# writer_attiny10.net
KiCad netlist of a schematic drawn in EAGLE
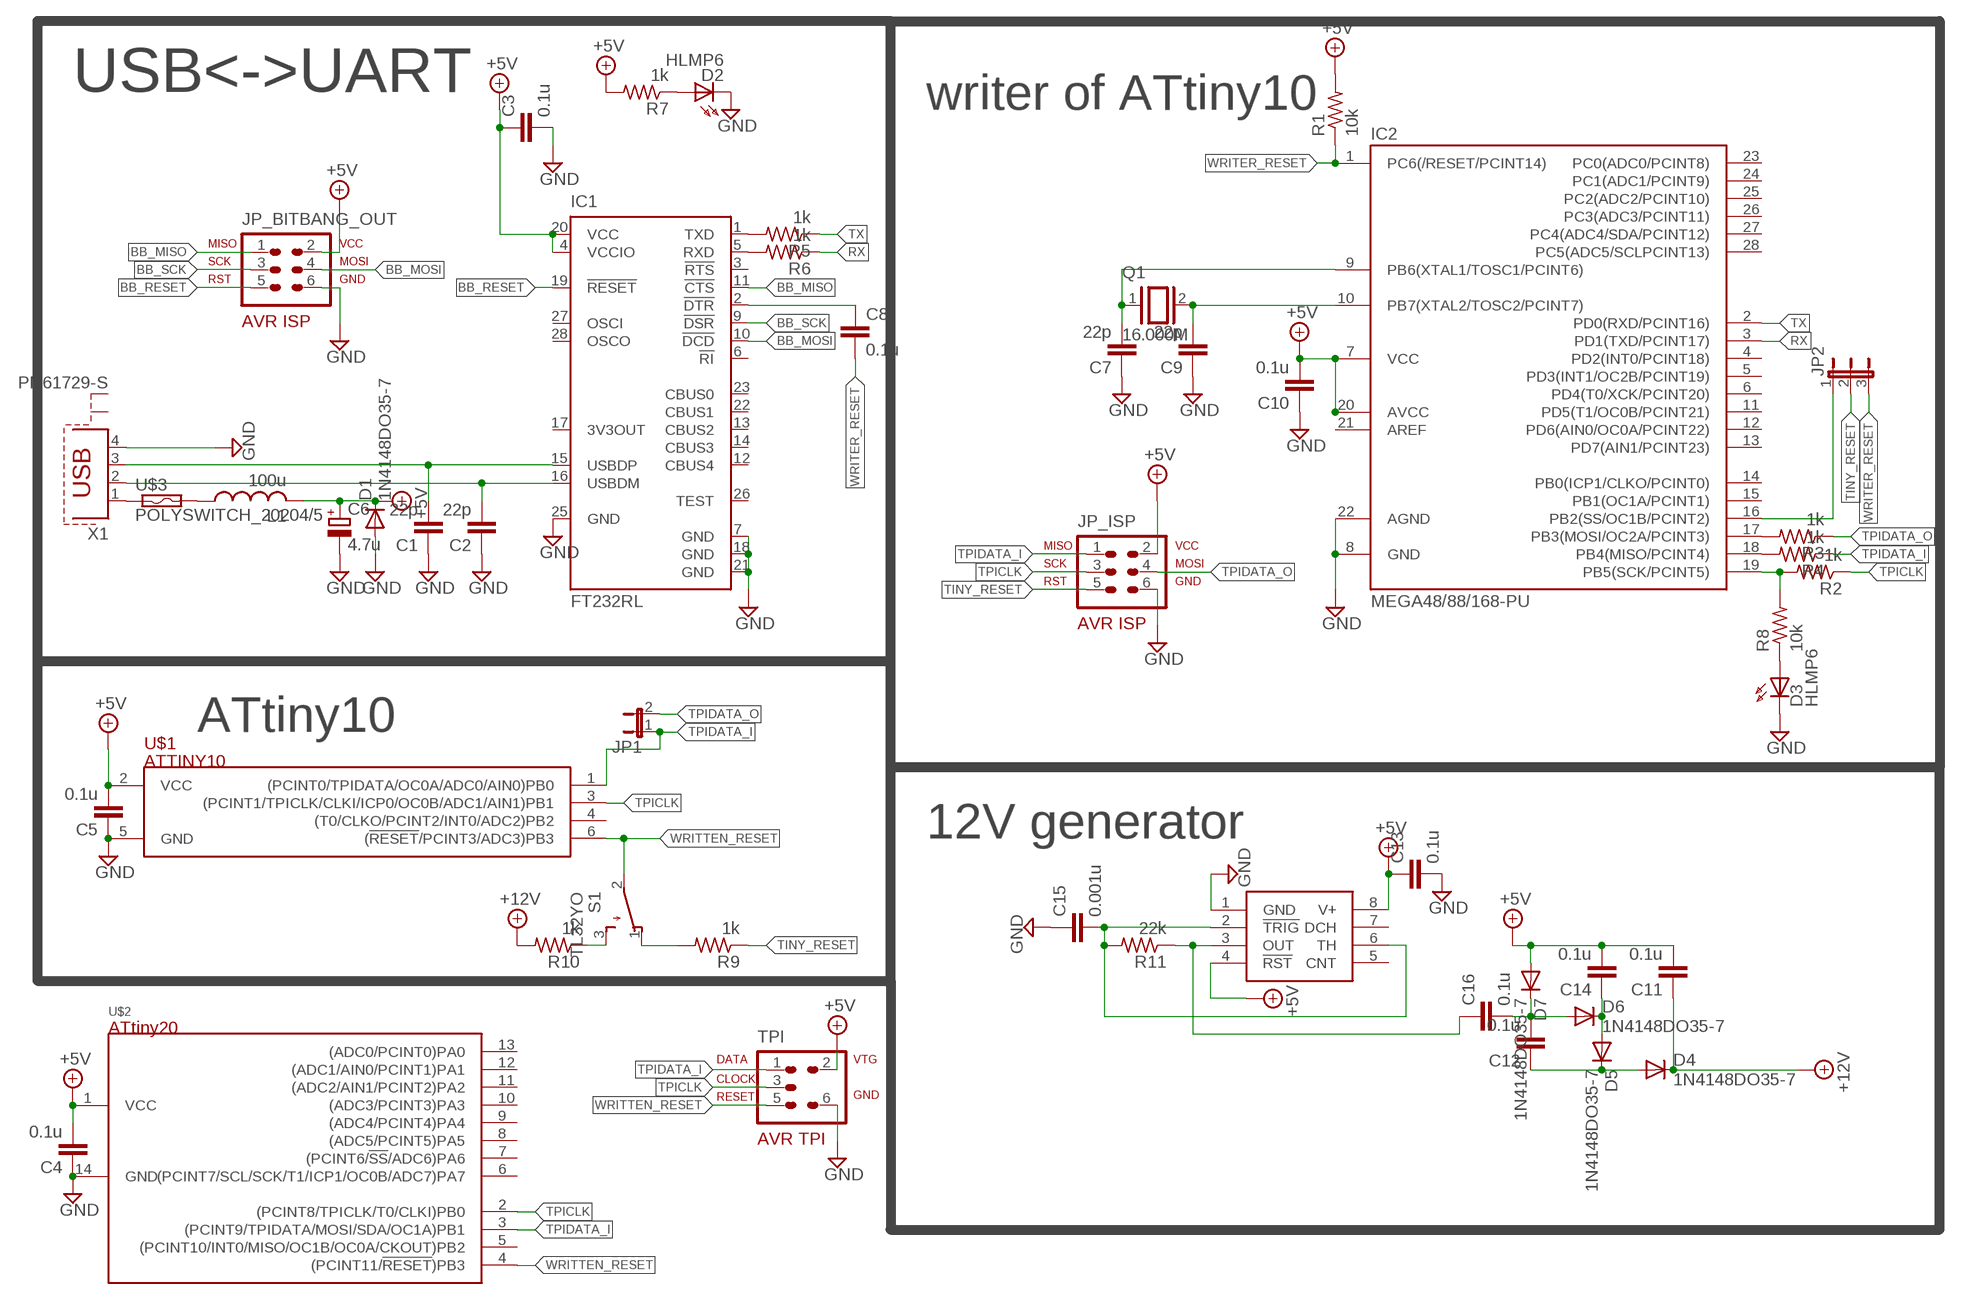
[diagram p0: schematic, sheet 1]

(export (version "E")
  (design (tool "Eeschema 10.0.6"))
  (components
    (comp (ref "C1")
      (value "22p")
      (footprint "eagle-import:C0603")
      (libsource (lib "eagle-import") (part "C-EUC0603"))
    )
    (comp (ref "C2")
      (value "22p")
      (footprint "eagle-import:C0603")
      (libsource (lib "eagle-import") (part "C-EUC0603"))
    )
    (comp (ref "C3")
      (value "0.1u")
      (footprint "eagle-import:C0603")
      (libsource (lib "eagle-import") (part "C-EUC0603"))
    )
    (comp (ref "C4")
      (value "0.1u")
      (footprint "eagle-import:C0603")
      (libsource (lib "eagle-import") (part "C-EUC0603"))
    )
    (comp (ref "C5")
      (value "0.1u")
      (footprint "eagle-import:C0603")
      (libsource (lib "eagle-import") (part "C-EUC0603"))
    )
    (comp (ref "C6")
      (value "4.7u")
      (footprint "eagle-import:CT3216")
      (libsource (lib "eagle-import") (part "CPOL-EUCT3216"))
    )
    (comp (ref "C7")
      (value "22p")
      (footprint "eagle-import:C0603")
      (libsource (lib "eagle-import") (part "C-EUC0603"))
    )
    (comp (ref "C8")
      (value "0.1u")
      (footprint "eagle-import:C0603")
      (libsource (lib "eagle-import") (part "C-EUC0603"))
    )
    (comp (ref "C9")
      (value "22p")
      (footprint "eagle-import:C0603")
      (libsource (lib "eagle-import") (part "C-EUC0603"))
    )
    (comp (ref "C10")
      (value "0.1u")
      (footprint "eagle-import:C0603")
      (libsource (lib "eagle-import") (part "C-EUC0603"))
    )
    (comp (ref "C11")
      (value "0.1u")
      (footprint "eagle-import:C0603")
      (libsource (lib "eagle-import") (part "C-EUC0603"))
    )
    (comp (ref "C12")
      (value "0.1u")
      (footprint "eagle-import:C0603")
      (libsource (lib "eagle-import") (part "C-EUC0603"))
    )
    (comp (ref "C13")
      (value "0.1u")
      (footprint "eagle-import:C0603")
      (libsource (lib "eagle-import") (part "C-EUC0603"))
    )
    (comp (ref "C14")
      (value "0.1u")
      (footprint "eagle-import:C0603")
      (libsource (lib "eagle-import") (part "C-EUC0603"))
    )
    (comp (ref "C15")
      (value "0.001u")
      (footprint "eagle-import:C0603")
      (libsource (lib "eagle-import") (part "C-EUC0603"))
    )
    (comp (ref "C16")
      (value "0.1u")
      (footprint "eagle-import:C0603")
      (libsource (lib "eagle-import") (part "C-EUC0603"))
    )
    (comp (ref "D1")
      (value "1N4148DO35-7")
      (footprint "eagle-import:DO35-7")
      (libsource (lib "eagle-import") (part "1N4148DO35-7"))
    )
    (comp (ref "D2")
      (value "HLMP6")
      (footprint "eagle-import:HLMP6")
      (fields
        (field (name "MF") "AGILENT TECHNOLOGIES")
        (field (name "MPN") "HLMP-6500")
        (field (name "MF_1") "AGILENT TECHNOLOGIES")
        (field (name "MPN_1") "HLMP-6500")
        (field (name "OC_FARNELL") "1652490")
        (field (name "OC_NEWARK") "40K0088")
      )
      (libsource (lib "eagle-import") (part "HLMP6"))
    )
    (comp (ref "D3")
      (value "HLMP6")
      (footprint "eagle-import:HLMP6")
      (fields (field (name "MF") "AGILENT TECHNOLOGIES") (field (name "MPN") "HLMP-6500"))
      (libsource (lib "eagle-import") (part "HLMP6"))
    )
    (comp (ref "D4")
      (value "1N4148DO35-7")
      (footprint "eagle-import:DO35-7")
      (libsource (lib "eagle-import") (part "1N4148DO35-7"))
    )
    (comp (ref "D5")
      (value "1N4148DO35-7")
      (footprint "eagle-import:DO35-7")
      (libsource (lib "eagle-import") (part "1N4148DO35-7"))
    )
    (comp (ref "D6")
      (value "1N4148DO35-7")
      (footprint "eagle-import:DO35-7")
      (libsource (lib "eagle-import") (part "1N4148DO35-7"))
    )
    (comp (ref "D7")
      (value "1N4148DO35-7")
      (footprint "eagle-import:DO35-7")
      (libsource (lib "eagle-import") (part "1N4148DO35-7"))
    )
    (comp (ref "IC1")
      (value "FT232RL")
      (footprint "eagle-import:SSOP28")
      (libsource (lib "eagle-import") (part "FT232RL"))
    )
    (comp (ref "IC2")
      (value "MEGA48/88/168-PU")
      (footprint "eagle-import:DIL28-3")
      (libsource (lib "eagle-import") (part "MEGA48/88/168-PU"))
    )
    (comp (ref "IC3")
      (value "LMC555")
      (footprint "eagle-import:DIL08")
      (libsource (lib "eagle-import") (part "LMC555"))
    )
    (comp (ref "JP1")
      (value "JP1E")
      (footprint "eagle-import:JP1")
      (libsource (lib "eagle-import") (part "JP1E"))
    )
    (comp (ref "JP2")
      (value "JP2E")
      (footprint "eagle-import:JP2")
      (libsource (lib "eagle-import") (part "JP2E"))
    )
    (comp (ref "JP_BITBANG_OUT")
      (value "AVR-ISP-6VERT")
      (footprint "eagle-import:AVR-ISP-6")
      (libsource (lib "eagle-import") (part "AVR-ISP-6VERT"))
    )
    (comp (ref "JP_ISP")
      (value "AVR-ISP-6VERT")
      (footprint "eagle-import:AVR-ISP-6")
      (libsource (lib "eagle-import") (part "AVR-ISP-6VERT"))
    )
    (comp (ref "L1")
      (value "100u")
      (footprint "eagle-import:0207_10")
      (libsource (lib "eagle-import") (part "L-US0207/10"))
    )
    (comp (ref "Q1")
      (value "16.000M")
      (footprint "eagle-import:QS")
      (libsource (lib "eagle-import") (part "XTAL/S"))
    )
    (comp (ref "R1")
      (value "10k")
      (footprint "eagle-import:R0603")
      (libsource (lib "eagle-import") (part "R-US_R0603"))
    )
    (comp (ref "R2")
      (value "1k")
      (footprint "eagle-import:R0603")
      (libsource (lib "eagle-import") (part "R-US_R0603"))
    )
    (comp (ref "R3")
      (value "1k")
      (footprint "eagle-import:R0603")
      (libsource (lib "eagle-import") (part "R-US_R0603"))
    )
    (comp (ref "R4")
      (value "1k")
      (footprint "eagle-import:R0603")
      (libsource (lib "eagle-import") (part "R-US_R0603"))
    )
    (comp (ref "R5")
      (value "1k")
      (footprint "eagle-import:R0603")
      (libsource (lib "eagle-import") (part "R-US_R0603"))
    )
    (comp (ref "R6")
      (value "1k")
      (footprint "eagle-import:R0603")
      (libsource (lib "eagle-import") (part "R-US_R0603"))
    )
    (comp (ref "R7")
      (value "1k")
      (footprint "eagle-import:R0603")
      (libsource (lib "eagle-import") (part "R-US_R0603"))
    )
    (comp (ref "R8")
      (value "10k")
      (footprint "eagle-import:R0603")
      (libsource (lib "eagle-import") (part "R-US_R0603"))
    )
    (comp (ref "R9")
      (value "1k")
      (footprint "eagle-import:R0603")
      (libsource (lib "eagle-import") (part "R-US_R0603"))
    )
    (comp (ref "R10")
      (value "1k")
      (footprint "eagle-import:R0603")
      (libsource (lib "eagle-import") (part "R-US_R0603"))
    )
    (comp (ref "R11")
      (value "22k")
      (footprint "eagle-import:R0603")
      (libsource (lib "eagle-import") (part "R-US_R0603"))
    )
    (comp (ref "S1")
      (value "TL32YO")
      (footprint "eagle-import:TL3XYO")
      (libsource (lib "eagle-import") (part "TL32YO"))
    )
    (comp (ref "TPI")
      (value "AVR-TPIVERT")
      (footprint "eagle-import:AVR-ISP-6")
      (libsource (lib "eagle-import") (part "AVR-TPIVERT"))
    )
    (comp (ref "U$1")
      (value "ATTINY10")
      (footprint "eagle-import:SOT-23")
      (libsource (lib "eagle-import") (part "ATTINY10"))
    )
    (comp (ref "U$2")
      (value "ATTINY20")
      (footprint "eagle-import:SOIC14")
      (libsource (lib "eagle-import") (part "ATTINY20"))
    )
    (comp (ref "U$3")
      (value "POLYSWITCH_20204/5")
      (footprint "eagle-import:0204_5")
      (libsource (lib "eagle-import") (part "POLYSWITCH_20204/5"))
    )
    (comp (ref "X1")
      (value "PN61729-S")
      (footprint "eagle-import:PN61729-S")
      (libsource (lib "eagle-import") (part "PN61729-S"))
    )
  )
  (nets
    (net (code "1") (name "+5V") (class "Default")
      (node (ref "C10") (pin "2") (pinfunction "2_2") (pintype "passive"))
      (node (ref "C11") (pin "2") (pinfunction "2_2") (pintype "passive"))
      (node (ref "C13") (pin "1") (pinfunction "1_1") (pintype "passive"))
      (node (ref "C14") (pin "2") (pinfunction "2_2") (pintype "passive"))
      (node (ref "C3") (pin "1") (pinfunction "1_1") (pintype "passive"))
      (node (ref "C4") (pin "2") (pinfunction "2_2") (pintype "passive"))
      (node (ref "C5") (pin "2") (pinfunction "2_2") (pintype "passive"))
      (node (ref "C6") (pin "+") (pinfunction "+_+") (pintype "passive"))
      (node (ref "D1") (pin "C") (pinfunction "C_C") (pintype "passive"))
      (node (ref "D7") (pin "A") (pinfunction "A_A") (pintype "passive"))
      (node (ref "IC1") (pin "20") (pinfunction "VCC_20") (pintype "power_in"))
      (node (ref "IC1") (pin "4") (pinfunction "VCCIO_4") (pintype "power_in"))
      (node (ref "IC2") (pin "20") (pinfunction "AVCC_20") (pintype "passive"))
      (node (ref "IC2") (pin "7") (pinfunction "VCC_7") (pintype "power_in"))
      (node (ref "IC3") (pin "4") (pinfunction "~{RST}_4") (pintype "bidirectional"))
      (node (ref "IC3") (pin "8") (pinfunction "V+_8") (pintype "bidirectional"))
      (node (ref "JP_BITBANG_OUT") (pin "2") (pinfunction "2_2") (pintype "passive"))
      (node (ref "JP_ISP") (pin "2") (pinfunction "2_2") (pintype "passive"))
      (node (ref "L1") (pin "2") (pinfunction "2_2") (pintype "passive"))
      (node (ref "R1") (pin "2") (pinfunction "2_2") (pintype "passive"))
      (node (ref "R7") (pin "2") (pinfunction "2_2") (pintype "passive"))
      (node (ref "TPI") (pin "2") (pinfunction "2_2") (pintype "passive"))
      (node (ref "U$1") (pin "2") (pinfunction "VCC_2") (pintype "power_in"))
      (node (ref "U$2") (pin "1") (pinfunction "VCC_1") (pintype "bidirectional"))
    )
    (net (code "2") (name "+12V") (class "Default")
      (node (ref "C11") (pin "1") (pinfunction "1_1") (pintype "passive"))
      (node (ref "D4") (pin "C") (pinfunction "C_C") (pintype "passive"))
      (node (ref "R10") (pin "2") (pinfunction "2_2") (pintype "passive"))
    )
    (net (code "3") (name "BB_MISO") (class "Default")
      (node (ref "IC1") (pin "11") (pinfunction "~{CTS}_11") (pintype "input"))
      (node (ref "JP_BITBANG_OUT") (pin "1") (pinfunction "1_1") (pintype "passive"))
    )
    (net (code "4") (name "BB_MOSI") (class "Default")
      (node (ref "IC1") (pin "10") (pinfunction "~{DCD}_10") (pintype "input"))
      (node (ref "JP_BITBANG_OUT") (pin "4") (pinfunction "4_4") (pintype "passive"))
    )
    (net (code "5") (name "BB_RESET") (class "Default")
      (node (ref "IC1") (pin "19") (pinfunction "~{RESET}_19") (pintype "input"))
      (node (ref "JP_BITBANG_OUT") (pin "5") (pinfunction "5_5") (pintype "passive"))
    )
    (net (code "6") (name "BB_SCK") (class "Default")
      (node (ref "IC1") (pin "9") (pinfunction "~{DSR}_9") (pintype "input"))
      (node (ref "JP_BITBANG_OUT") (pin "3") (pinfunction "3_3") (pintype "passive"))
    )
    (net (code "7") (name "GND") (class "Default")
      (node (ref "C1") (pin "1") (pinfunction "1_1") (pintype "passive"))
      (node (ref "C10") (pin "1") (pinfunction "1_1") (pintype "passive"))
      (node (ref "C13") (pin "2") (pinfunction "2_2") (pintype "passive"))
      (node (ref "C15") (pin "1") (pinfunction "1_1") (pintype "passive"))
      (node (ref "C2") (pin "1") (pinfunction "1_1") (pintype "passive"))
      (node (ref "C3") (pin "2") (pinfunction "2_2") (pintype "passive"))
      (node (ref "C4") (pin "1") (pinfunction "1_1") (pintype "passive"))
      (node (ref "C5") (pin "1") (pinfunction "1_1") (pintype "passive"))
      (node (ref "C6") (pin "-") (pinfunction "-_-") (pintype "passive"))
      (node (ref "C7") (pin "1") (pinfunction "1_1") (pintype "passive"))
      (node (ref "C9") (pin "1") (pinfunction "1_1") (pintype "passive"))
      (node (ref "D1") (pin "A") (pinfunction "A_A") (pintype "passive"))
      (node (ref "D2") (pin "K") (pinfunction "K_K") (pintype "passive"))
      (node (ref "D3") (pin "K") (pinfunction "K_K") (pintype "passive"))
      (node (ref "IC1") (pin "18") (pinfunction "GND_18") (pintype "power_in"))
      (node (ref "IC1") (pin "21") (pinfunction "GND_21") (pintype "power_in"))
      (node (ref "IC1") (pin "25") (pinfunction "GND_25") (pintype "power_in"))
      (node (ref "IC1") (pin "7") (pinfunction "GND_7") (pintype "power_in"))
      (node (ref "IC2") (pin "22") (pinfunction "AGND_22") (pintype "power_in"))
      (node (ref "IC2") (pin "8") (pinfunction "GND_8") (pintype "power_in"))
      (node (ref "IC3") (pin "1") (pinfunction "GND_1") (pintype "bidirectional"))
      (node (ref "JP_BITBANG_OUT") (pin "6") (pinfunction "6_6") (pintype "passive"))
      (node (ref "JP_ISP") (pin "6") (pinfunction "6_6") (pintype "passive"))
      (node (ref "TPI") (pin "6") (pinfunction "6_6") (pintype "passive"))
      (node (ref "U$1") (pin "5") (pinfunction "GND_5") (pintype "power_in"))
      (node (ref "U$2") (pin "14") (pinfunction "GND_14") (pintype "bidirectional"))
      (node (ref "X1") (pin "4") (pinfunction "4_4") (pintype "passive"))
    )
    (net (code "8") (name "Net-(C12-Pad1)") (class "Default")
      (node (ref "C12") (pin "1") (pinfunction "1_1") (pintype "passive"))
      (node (ref "D4") (pin "A") (pinfunction "A_A") (pintype "passive"))
      (node (ref "D5") (pin "C") (pinfunction "C_C") (pintype "passive"))
    )
    (net (code "9") (name "Net-(C12-Pad2)") (class "Default")
      (node (ref "C12") (pin "2") (pinfunction "2_2") (pintype "passive"))
      (node (ref "C16") (pin "2") (pinfunction "2_2") (pintype "passive"))
      (node (ref "D6") (pin "A") (pinfunction "A_A") (pintype "passive"))
      (node (ref "D7") (pin "C") (pinfunction "C_C") (pintype "passive"))
    )
    (net (code "10") (name "Net-(C14-Pad1)") (class "Default")
      (node (ref "C14") (pin "1") (pinfunction "1_1") (pintype "passive"))
      (node (ref "D5") (pin "A") (pinfunction "A_A") (pintype "passive"))
      (node (ref "D6") (pin "C") (pinfunction "C_C") (pintype "passive"))
    )
    (net (code "11") (name "Net-(D2-PadA)") (class "Default")
      (node (ref "D2") (pin "A") (pinfunction "A_A") (pintype "passive"))
      (node (ref "R7") (pin "1") (pinfunction "1_1") (pintype "passive"))
    )
    (net (code "12") (name "Net-(D3-PadA)") (class "Default")
      (node (ref "D3") (pin "A") (pinfunction "A_A") (pintype "passive"))
      (node (ref "R8") (pin "1") (pinfunction "1_1") (pintype "passive"))
    )
    (net (code "13") (name "Net-(IC1-RXD)") (class "Default")
      (node (ref "IC1") (pin "5") (pinfunction "RXD_5") (pintype "input"))
      (node (ref "R6") (pin "2") (pinfunction "2_2") (pintype "passive"))
    )
    (net (code "14") (name "Net-(IC1-TXD)") (class "Default")
      (node (ref "IC1") (pin "1") (pinfunction "TXD_1") (pintype "output"))
      (node (ref "R5") (pin "2") (pinfunction "2_2") (pintype "passive"))
    )
    (net (code "15") (name "Net-(IC1-USBDM)") (class "Default")
      (node (ref "C2") (pin "2") (pinfunction "2_2") (pintype "passive"))
      (node (ref "IC1") (pin "16") (pinfunction "USBDM_16") (pintype "bidirectional"))
      (node (ref "X1") (pin "2") (pinfunction "2_2") (pintype "passive"))
    )
    (net (code "16") (name "Net-(IC1-USBDP)") (class "Default")
      (node (ref "C1") (pin "2") (pinfunction "2_2") (pintype "passive"))
      (node (ref "IC1") (pin "15") (pinfunction "USBDP_15") (pintype "bidirectional"))
      (node (ref "X1") (pin "3") (pinfunction "3_3") (pintype "passive"))
    )
    (net (code "17") (name "Net-(IC1-~{DTR})") (class "Default")
      (node (ref "C8") (pin "1") (pinfunction "1_1") (pintype "passive"))
      (node (ref "IC1") (pin "2") (pinfunction "~{DTR}_2") (pintype "output"))
    )
    (net (code "18") (name "Net-(IC2-PB2(SS{slash}OC1B{slash}PCINT2))") (class "Default")
      (node (ref "IC2") (pin "16") (pinfunction "PB2(SS/OC1B/PCINT2)_16") (pintype "bidirectional"))
      (node (ref "JP2") (pin "1") (pinfunction "1_1") (pintype "passive"))
    )
    (net (code "19") (name "Net-(IC2-PB3(MOSI{slash}OC2A{slash}PCINT3))") (class "Default")
      (node (ref "IC2") (pin "17") (pinfunction "PB3(MOSI/OC2A/PCINT3)_17") (pintype "bidirectional"))
      (node (ref "R3") (pin "2") (pinfunction "2_2") (pintype "passive"))
    )
    (net (code "20") (name "Net-(IC2-PB4(MISO{slash}PCINT4))") (class "Default")
      (node (ref "IC2") (pin "18") (pinfunction "PB4(MISO/PCINT4)_18") (pintype "bidirectional"))
      (node (ref "R4") (pin "2") (pinfunction "2_2") (pintype "passive"))
    )
    (net (code "21") (name "Net-(IC2-PB5(SCK{slash}PCINT5))") (class "Default")
      (node (ref "IC2") (pin "19") (pinfunction "PB5(SCK/PCINT5)_19") (pintype "bidirectional"))
      (node (ref "R2") (pin "2") (pinfunction "2_2") (pintype "passive"))
      (node (ref "R8") (pin "2") (pinfunction "2_2") (pintype "passive"))
    )
    (net (code "22") (name "Net-(IC2-PB6(XTAL1{slash}TOSC1{slash}PCINT6))") (class "Default")
      (node (ref "C7") (pin "2") (pinfunction "2_2") (pintype "passive"))
      (node (ref "IC2") (pin "9") (pinfunction "PB6(XTAL1/TOSC1/PCINT6)_9") (pintype "bidirectional"))
      (node (ref "Q1") (pin "1") (pinfunction "1_1") (pintype "passive"))
    )
    (net (code "23") (name "Net-(IC2-PB7(XTAL2{slash}TOSC2{slash}PCINT7))") (class "Default")
      (node (ref "C9") (pin "2") (pinfunction "2_2") (pintype "passive"))
      (node (ref "IC2") (pin "10") (pinfunction "PB7(XTAL2/TOSC2/PCINT7)_10") (pintype "bidirectional"))
      (node (ref "Q1") (pin "2") (pinfunction "2_2") (pintype "passive"))
    )
    (net (code "24") (name "Net-(IC3-OUT)") (class "Default")
      (node (ref "C16") (pin "1") (pinfunction "1_1") (pintype "passive"))
      (node (ref "IC3") (pin "3") (pinfunction "OUT_3") (pintype "bidirectional"))
      (node (ref "R11") (pin "1") (pinfunction "1_1") (pintype "passive"))
    )
    (net (code "25") (name "Net-(IC3-TH)") (class "Default")
      (node (ref "C15") (pin "2") (pinfunction "2_2") (pintype "passive"))
      (node (ref "IC3") (pin "2") (pinfunction "~{TRIG}_2") (pintype "bidirectional"))
      (node (ref "IC3") (pin "6") (pinfunction "TH_6") (pintype "bidirectional"))
      (node (ref "R11") (pin "2") (pinfunction "2_2") (pintype "passive"))
    )
    (net (code "26") (name "Net-(L1-Pad1)") (class "Default")
      (node (ref "L1") (pin "1") (pinfunction "1_1") (pintype "passive"))
      (node (ref "U$3") (pin "2") (pinfunction "2_2") (pintype "passive"))
    )
    (net (code "27") (name "Net-(S1-O)") (class "Default")
      (node (ref "R9") (pin "2") (pinfunction "2_2") (pintype "passive"))
      (node (ref "S1") (pin "1") (pinfunction "O_1") (pintype "passive"))
    )
    (net (code "28") (name "Net-(S1-S)") (class "Default")
      (node (ref "R10") (pin "1") (pinfunction "1_1") (pintype "passive"))
      (node (ref "S1") (pin "3") (pinfunction "S_3") (pintype "passive"))
    )
    (net (code "29") (name "Net-(U$3-Pad1)") (class "Default")
      (node (ref "U$3") (pin "1") (pinfunction "1_1") (pintype "passive"))
      (node (ref "X1") (pin "1") (pinfunction "1_1") (pintype "passive"))
    )
    (net (code "30") (name "RX") (class "Default")
      (node (ref "IC2") (pin "3") (pinfunction "PD1(TXD/PCINT17)_3") (pintype "bidirectional"))
      (node (ref "R6") (pin "1") (pinfunction "1_1") (pintype "passive"))
    )
    (net (code "31") (name "TINY_RESET") (class "Default")
      (node (ref "JP2") (pin "2") (pinfunction "2_2") (pintype "passive"))
      (node (ref "JP_ISP") (pin "5") (pinfunction "5_5") (pintype "passive"))
      (node (ref "R9") (pin "1") (pinfunction "1_1") (pintype "passive"))
    )
    (net (code "32") (name "TPICLK") (class "Default")
      (node (ref "JP_ISP") (pin "3") (pinfunction "3_3") (pintype "passive"))
      (node (ref "R2") (pin "1") (pinfunction "1_1") (pintype "passive"))
      (node (ref "TPI") (pin "3") (pinfunction "3_3") (pintype "passive"))
      (node (ref "U$1") (pin "3") (pinfunction "(PCINT1/TPICLK/CLKI/ICP0/OC0B/ADC1/AIN1)PB1_3") (pintype "bidirectional"))
      (node (ref "U$2") (pin "2") (pinfunction "(PCINT8/TPICLK/T0/CLKI)PB0_2") (pintype "bidirectional"))
    )
    (net (code "33") (name "TPIDATA_I") (class "Default")
      (node (ref "JP1") (pin "1") (pinfunction "1_1") (pintype "passive"))
      (node (ref "JP_ISP") (pin "1") (pinfunction "1_1") (pintype "passive"))
      (node (ref "R4") (pin "1") (pinfunction "1_1") (pintype "passive"))
      (node (ref "TPI") (pin "1") (pinfunction "1_1") (pintype "passive"))
      (node (ref "U$1") (pin "1") (pinfunction "(PCINT0/TPIDATA/OC0A/ADC0/AIN0)PB0_1") (pintype "bidirectional"))
      (node (ref "U$2") (pin "3") (pinfunction "(PCINT9/TPIDATA/MOSI/SDA/OC1A)PB1_3") (pintype "bidirectional"))
    )
    (net (code "34") (name "TPIDATA_O") (class "Default")
      (node (ref "JP1") (pin "2") (pinfunction "2_2") (pintype "passive"))
      (node (ref "JP_ISP") (pin "4") (pinfunction "4_4") (pintype "passive"))
      (node (ref "R3") (pin "1") (pinfunction "1_1") (pintype "passive"))
    )
    (net (code "35") (name "TX") (class "Default")
      (node (ref "IC2") (pin "2") (pinfunction "PD0(RXD/PCINT16)_2") (pintype "bidirectional"))
      (node (ref "R5") (pin "1") (pinfunction "1_1") (pintype "passive"))
    )
    (net (code "36") (name "WRITER_RESET") (class "Default")
      (node (ref "C8") (pin "2") (pinfunction "2_2") (pintype "passive"))
      (node (ref "IC2") (pin "1") (pinfunction "PC6(/RESET/PCINT14)_1") (pintype "bidirectional"))
      (node (ref "JP2") (pin "3") (pinfunction "3_3") (pintype "passive"))
      (node (ref "R1") (pin "1") (pinfunction "1_1") (pintype "passive"))
    )
    (net (code "37") (name "WRITTEN_RESET") (class "Default")
      (node (ref "S1") (pin "2") (pinfunction "P_2") (pintype "passive"))
      (node (ref "TPI") (pin "5") (pinfunction "5_5") (pintype "passive"))
      (node (ref "U$1") (pin "6") (pinfunction "(~{RESET}/PCINT3/ADC3)PB3_6") (pintype "bidirectional"))
      (node (ref "U$2") (pin "4") (pinfunction "(PCINT11/~{RESET})PB3_4") (pintype "bidirectional"))
    )
    (net (code "38") (name "unconnected-(IC1-3V3OUT-Pad17)") (class "Default")
      (node (ref "IC1") (pin "17") (pinfunction "3V3OUT_17") (pintype "output"))
    )
    (net (code "39") (name "unconnected-(IC1-CBUS0-Pad23)") (class "Default")
      (node (ref "IC1") (pin "23") (pinfunction "CBUS0_23") (pintype "bidirectional"))
    )
    (net (code "40") (name "unconnected-(IC1-CBUS1-Pad22)") (class "Default")
      (node (ref "IC1") (pin "22") (pinfunction "CBUS1_22") (pintype "bidirectional"))
    )
    (net (code "41") (name "unconnected-(IC1-CBUS2-Pad13)") (class "Default")
      (node (ref "IC1") (pin "13") (pinfunction "CBUS2_13") (pintype "bidirectional"))
    )
    (net (code "42") (name "unconnected-(IC1-CBUS3-Pad14)") (class "Default")
      (node (ref "IC1") (pin "14") (pinfunction "CBUS3_14") (pintype "bidirectional"))
    )
    (net (code "43") (name "unconnected-(IC1-CBUS4-Pad12)") (class "Default")
      (node (ref "IC1") (pin "12") (pinfunction "CBUS4_12") (pintype "bidirectional"))
    )
    (net (code "44") (name "unconnected-(IC1-OSCI-Pad27)") (class "Default")
      (node (ref "IC1") (pin "27") (pinfunction "OSCI_27") (pintype "input"))
    )
    (net (code "45") (name "unconnected-(IC1-OSCO-Pad28)") (class "Default")
      (node (ref "IC1") (pin "28") (pinfunction "OSCO_28") (pintype "output"))
    )
    (net (code "46") (name "unconnected-(IC1-TEST-Pad26)") (class "Default")
      (node (ref "IC1") (pin "26") (pinfunction "TEST_26") (pintype "input"))
    )
    (net (code "47") (name "unconnected-(IC1-~{RI}-Pad6)") (class "Default")
      (node (ref "IC1") (pin "6") (pinfunction "~{RI}_6") (pintype "input"))
    )
    (net (code "48") (name "unconnected-(IC1-~{RTS}-Pad3)") (class "Default")
      (node (ref "IC1") (pin "3") (pinfunction "~{RTS}_3") (pintype "output"))
    )
    (net (code "49") (name "unconnected-(IC2-AREF-Pad21)") (class "Default")
      (node (ref "IC2") (pin "21") (pinfunction "AREF_21") (pintype "passive"))
    )
    (net (code "50") (name "unconnected-(IC2-PB0(ICP1{slash}CLKO{slash}PCINT0)-Pad14)") (class "Default")
      (node (ref "IC2") (pin "14") (pinfunction "PB0(ICP1/CLKO/PCINT0)_14") (pintype "bidirectional"))
    )
    (net (code "51") (name "unconnected-(IC2-PB1(OC1A{slash}PCINT1)-Pad15)") (class "Default")
      (node (ref "IC2") (pin "15") (pinfunction "PB1(OC1A/PCINT1)_15") (pintype "bidirectional"))
    )
    (net (code "52") (name "unconnected-(IC2-PC0(ADC0{slash}PCINT8)-Pad23)") (class "Default")
      (node (ref "IC2") (pin "23") (pinfunction "PC0(ADC0/PCINT8)_23") (pintype "bidirectional"))
    )
    (net (code "53") (name "unconnected-(IC2-PC1(ADC1{slash}PCINT9)-Pad24)") (class "Default")
      (node (ref "IC2") (pin "24") (pinfunction "PC1(ADC1/PCINT9)_24") (pintype "bidirectional"))
    )
    (net (code "54") (name "unconnected-(IC2-PC2(ADC2{slash}PCINT10)-Pad25)") (class "Default")
      (node (ref "IC2") (pin "25") (pinfunction "PC2(ADC2/PCINT10)_25") (pintype "bidirectional"))
    )
    (net (code "55") (name "unconnected-(IC2-PC3(ADC3{slash}PCINT11)-Pad26)") (class "Default")
      (node (ref "IC2") (pin "26") (pinfunction "PC3(ADC3/PCINT11)_26") (pintype "bidirectional"))
    )
    (net (code "56") (name "unconnected-(IC2-PC4(ADC4{slash}SDA{slash}PCINT12)-Pad27)") (class "Default")
      (node (ref "IC2") (pin "27") (pinfunction "PC4(ADC4/SDA/PCINT12)_27") (pintype "bidirectional"))
    )
    (net (code "57") (name "unconnected-(IC2-PC5(ADC5{slash}SCLPCINT13)-Pad28)") (class "Default")
      (node (ref "IC2") (pin "28") (pinfunction "PC5(ADC5/SCLPCINT13)_28") (pintype "bidirectional"))
    )
    (net (code "58") (name "unconnected-(IC2-PD2(INT0{slash}PCINT18)-Pad4)") (class "Default")
      (node (ref "IC2") (pin "4") (pinfunction "PD2(INT0/PCINT18)_4") (pintype "bidirectional"))
    )
    (net (code "59") (name "unconnected-(IC2-PD3(INT1{slash}OC2B{slash}PCINT19)-Pad5)") (class "Default")
      (node (ref "IC2") (pin "5") (pinfunction "PD3(INT1/OC2B/PCINT19)_5") (pintype "bidirectional"))
    )
    (net (code "60") (name "unconnected-(IC2-PD4(T0{slash}XCK{slash}PCINT20)-Pad6)") (class "Default")
      (node (ref "IC2") (pin "6") (pinfunction "PD4(T0/XCK/PCINT20)_6") (pintype "bidirectional"))
    )
    (net (code "61") (name "unconnected-(IC2-PD5(T1{slash}OC0B{slash}PCINT21)-Pad11)") (class "Default")
      (node (ref "IC2") (pin "11") (pinfunction "PD5(T1/OC0B/PCINT21)_11") (pintype "bidirectional"))
    )
    (net (code "62") (name "unconnected-(IC2-PD6(AIN0{slash}OC0A{slash}PCINT22)-Pad12)") (class "Default")
      (node (ref "IC2") (pin "12") (pinfunction "PD6(AIN0/OC0A/PCINT22)_12") (pintype "bidirectional"))
    )
    (net (code "63") (name "unconnected-(IC2-PD7(AIN1{slash}PCINT23)-Pad13)") (class "Default")
      (node (ref "IC2") (pin "13") (pinfunction "PD7(AIN1/PCINT23)_13") (pintype "bidirectional"))
    )
    (net (code "64") (name "unconnected-(IC3-CNT-Pad5)") (class "Default")
      (node (ref "IC3") (pin "5") (pinfunction "CNT_5") (pintype "bidirectional"))
    )
    (net (code "65") (name "unconnected-(IC3-DCH-Pad7)") (class "Default")
      (node (ref "IC3") (pin "7") (pinfunction "DCH_7") (pintype "bidirectional"))
    )
    (net (code "66") (name "unconnected-(U$1-(T0{slash}CLKO{slash}PCINT2{slash}INT0{slash}ADC2)PB2-Pad4)") (class "Default")
      (node (ref "U$1") (pin "4") (pinfunction "(T0/CLKO/PCINT2/INT0/ADC2)PB2_4") (pintype "bidirectional"))
    )
    (net (code "67") (name "unconnected-(U$2-(ADC0{slash}PCINT0)PA0-Pad13)") (class "Default")
      (node (ref "U$2") (pin "13") (pinfunction "(ADC0/PCINT0)PA0_13") (pintype "bidirectional"))
    )
    (net (code "68") (name "unconnected-(U$2-(ADC1{slash}AIN0{slash}PCINT1)PA1-Pad12)") (class "Default")
      (node (ref "U$2") (pin "12") (pinfunction "(ADC1/AIN0/PCINT1)PA1_12") (pintype "bidirectional"))
    )
    (net (code "69") (name "unconnected-(U$2-(ADC2{slash}AIN1{slash}PCINT2)PA2-Pad11)") (class "Default")
      (node (ref "U$2") (pin "11") (pinfunction "(ADC2/AIN1/PCINT2)PA2_11") (pintype "bidirectional"))
    )
    (net (code "70") (name "unconnected-(U$2-(ADC3{slash}PCINT3)PA3-Pad10)") (class "Default")
      (node (ref "U$2") (pin "10") (pinfunction "(ADC3/PCINT3)PA3_10") (pintype "bidirectional"))
    )
    (net (code "71") (name "unconnected-(U$2-(ADC4{slash}PCINT4)PA4-Pad9)") (class "Default")
      (node (ref "U$2") (pin "9") (pinfunction "(ADC4/PCINT4)PA4_9") (pintype "bidirectional"))
    )
    (net (code "72") (name "unconnected-(U$2-(ADC5{slash}PCINT5)PA5-Pad8)") (class "Default")
      (node (ref "U$2") (pin "8") (pinfunction "(ADC5/PCINT5)PA5_8") (pintype "bidirectional"))
    )
    (net (code "73") (name "unconnected-(U$2-(PCINT6{slash}~{SS}{slash}ADC6)PA6-Pad7)") (class "Default")
      (node (ref "U$2") (pin "7") (pinfunction "(PCINT6/~{SS}/ADC6)PA6_7") (pintype "bidirectional"))
    )
    (net (code "74") (name "unconnected-(U$2-(PCINT7{slash}SCL{slash}SCK{slash}T1{slash}ICP1{slash}OC0B{slash}ADC7)PA7-Pad6)") (class "Default")
      (node (ref "U$2") (pin "6") (pinfunction "(PCINT7/SCL/SCK/T1/ICP1/OC0B/ADC7)PA7_6") (pintype "bidirectional"))
    )
    (net (code "75") (name "unconnected-(U$2-(PCINT10{slash}INT0{slash}MISO{slash}OC1B{slash}OC0A{slash}CKOUT)PB2-Pad5)") (class "Default")
      (node (ref "U$2") (pin "5") (pinfunction "(PCINT10/INT0/MISO/OC1B/OC0A/CKOUT)PB2_5") (pintype "bidirectional"))
    )
    (net (code "76") (name "unconnected-(X1-PadS1)") (class "Default")
      (node (ref "X1") (pin "S1") (pinfunction "S1_S1") (pintype "passive"))
    )
    (net (code "77") (name "unconnected-(X1-PadS2)") (class "Default")
      (node (ref "X1") (pin "S2") (pinfunction "S2_S2") (pintype "passive"))
    )
  )
)
